# v4m.net
KiCad netlist of a schematic drawn in EAGLE
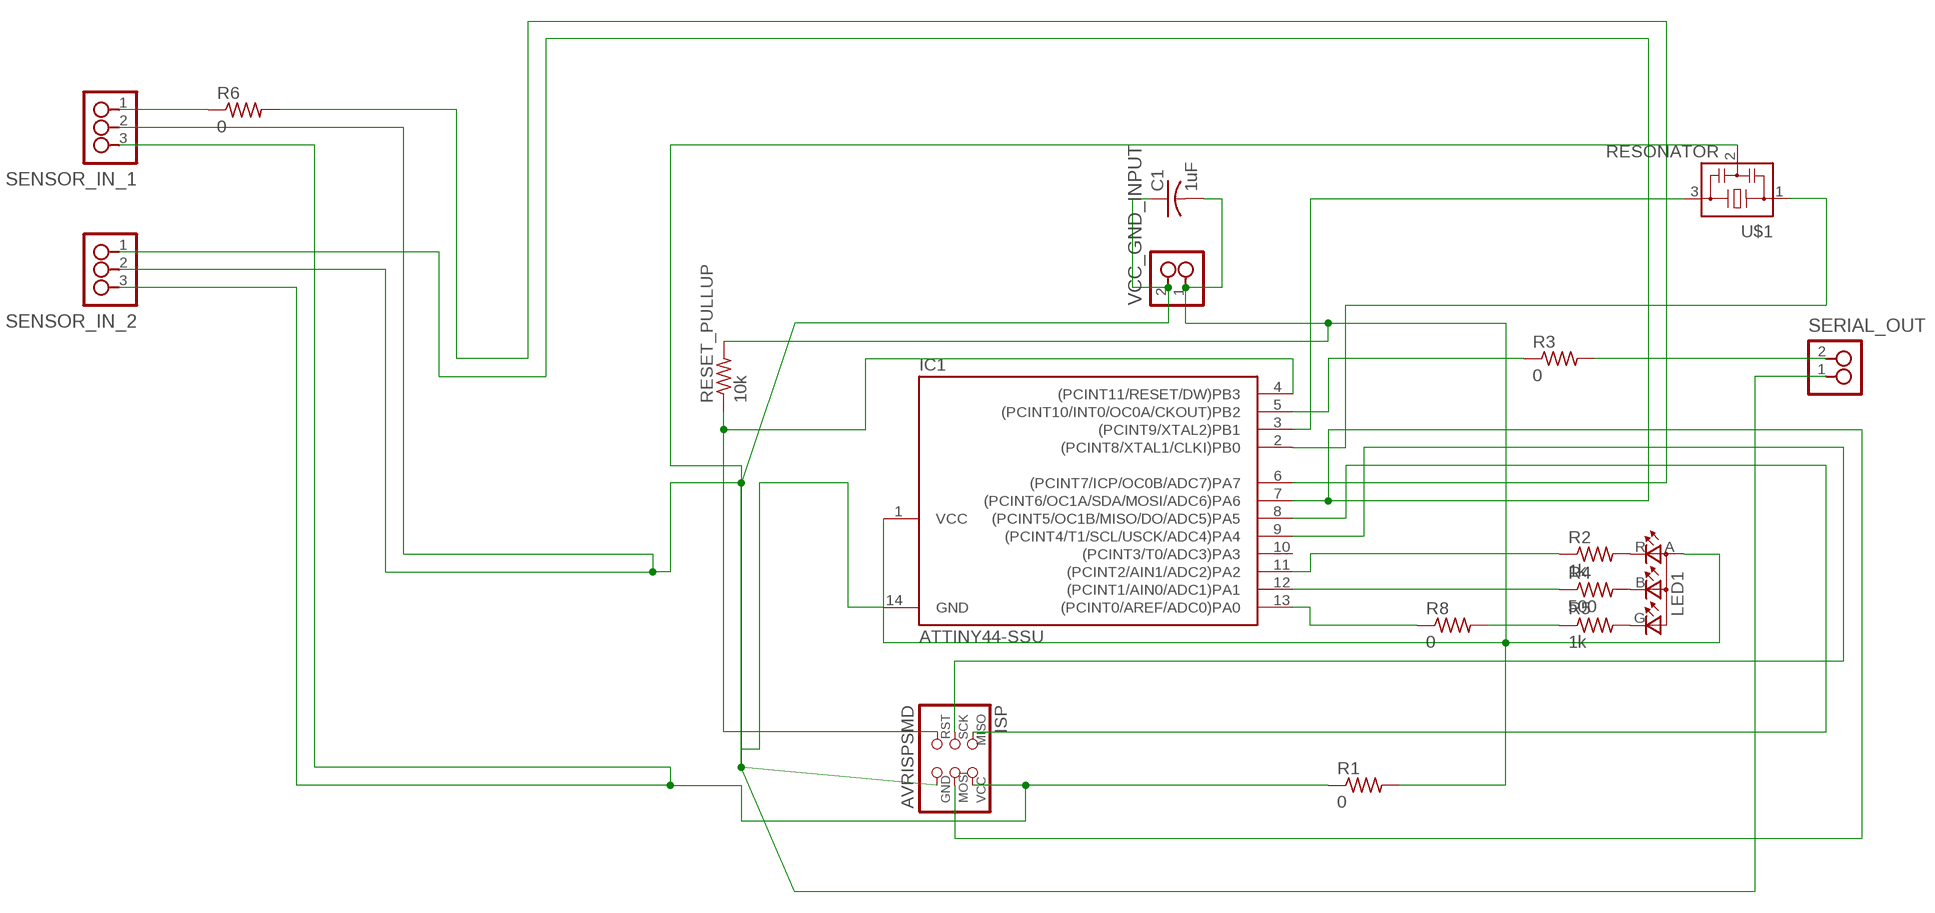
[diagram p0: schematic, sheet 1]

(export (version "E")
  (design (tool "Eeschema 10.0.6"))
  (components
    (comp (ref "C1")
      (value "1uF")
      (footprint "eagle-import:C1206")
      (libsource (lib "eagle-import") (part "C-USC1206"))
    )
    (comp (ref "IC1")
      (value "ATTINY44-SSU")
      (footprint "eagle-import:SOIC14")
      (libsource (lib "eagle-import") (part "ATTINY44-SSU"))
    )
    (comp (ref "ISP")
      (value "AVRISPSMD")
      (footprint "eagle-import:2X03SMD")
      (libsource (lib "eagle-import") (part "AVRISPSMD"))
    )
    (comp (ref "LED1")
      (value "LEDRGBOLD")
      (footprint "eagle-import:P-LCC-4-3")
      (libsource (lib "eagle-import") (part "LEDRGBOLD"))
    )
    (comp (ref "R1")
      (value "0")
      (footprint "eagle-import:R1206")
      (libsource (lib "eagle-import") (part "RES-US1206"))
    )
    (comp (ref "R2")
      (value "1k")
      (footprint "eagle-import:R1206")
      (libsource (lib "eagle-import") (part "RES-US1206"))
    )
    (comp (ref "R3")
      (value "0")
      (footprint "eagle-import:R1206")
      (libsource (lib "eagle-import") (part "RES-US1206"))
    )
    (comp (ref "R4")
      (value "500")
      (footprint "eagle-import:R1206")
      (libsource (lib "eagle-import") (part "RES-US1206"))
    )
    (comp (ref "R5")
      (value "1k")
      (footprint "eagle-import:R1206")
      (libsource (lib "eagle-import") (part "RES-US1206"))
    )
    (comp (ref "R6")
      (value "0")
      (footprint "eagle-import:R1206")
      (libsource (lib "eagle-import") (part "RES-US1206"))
    )
    (comp (ref "R8")
      (value "0")
      (footprint "eagle-import:R1206")
      (libsource (lib "eagle-import") (part "RES-US1206"))
    )
    (comp (ref "RESET_PULLUP")
      (value "10k")
      (footprint "eagle-import:R1206")
      (libsource (lib "eagle-import") (part "R-US_R1206"))
    )
    (comp (ref "SENSOR_IN_1")
      (value "3_PIN_HEADERHEADER")
      (footprint "eagle-import:SMT_PINS_3")
      (libsource (lib "eagle-import") (part "3_PIN_HEADERHEADER"))
    )
    (comp (ref "SENSOR_IN_2")
      (value "3_PIN_HEADERHEADER")
      (footprint "eagle-import:SMT_PINS_3")
      (libsource (lib "eagle-import") (part "3_PIN_HEADERHEADER"))
    )
    (comp (ref "SERIAL_OUT")
      (value "2_PIN_HEADERHEADER")
      (footprint "eagle-import:SMT_PINS_2")
      (libsource (lib "eagle-import") (part "2_PIN_HEADERHEADER"))
    )
    (comp (ref "U$1")
      (value "RESONATOR")
      (footprint "eagle-import:EFOBM")
      (libsource (lib "eagle-import") (part "RESONATOR"))
    )
    (comp (ref "VCC_GND_INPUT")
      (value "2_PIN_HEADERHEADER")
      (footprint "eagle-import:SMT_PINS_2")
      (libsource (lib "eagle-import") (part "2_PIN_HEADERHEADER"))
    )
  )
  (nets
    (net (code "1") (name "Net-(IC1-(PCINT0{slash}AREF{slash}ADC0)PA0)") (class "Default")
      (node (ref "IC1") (pin "13") (pinfunction "(PCINT0/AREF/ADC0)PA0_13") (pintype "bidirectional"))
      (node (ref "R8") (pin "1") (pinfunction "1_1") (pintype "passive"))
    )
    (net (code "2") (name "Net-(IC1-(PCINT1{slash}AIN0{slash}ADC1)PA1)") (class "Default")
      (node (ref "IC1") (pin "12") (pinfunction "(PCINT1/AIN0/ADC1)PA1_12") (pintype "bidirectional"))
      (node (ref "R4") (pin "1") (pinfunction "1_1") (pintype "passive"))
    )
    (net (code "3") (name "Net-(IC1-(PCINT2{slash}AIN1{slash}ADC2)PA2)") (class "Default")
      (node (ref "IC1") (pin "11") (pinfunction "(PCINT2/AIN1/ADC2)PA2_11") (pintype "bidirectional"))
      (node (ref "R2") (pin "1") (pinfunction "1_1") (pintype "passive"))
    )
    (net (code "4") (name "Net-(IC1-(PCINT4{slash}T1{slash}SCL{slash}USCK{slash}ADC4)PA4)") (class "Default")
      (node (ref "IC1") (pin "9") (pinfunction "(PCINT4/T1/SCL/USCK/ADC4)PA4_9") (pintype "bidirectional"))
      (node (ref "ISP") (pin "3") (pinfunction "SCK_3") (pintype "passive"))
    )
    (net (code "5") (name "Net-(IC1-(PCINT5{slash}OC1B{slash}MISO{slash}DO{slash}ADC5)PA5)") (class "Default")
      (node (ref "IC1") (pin "8") (pinfunction "(PCINT5/OC1B/MISO/DO/ADC5)PA5_8") (pintype "bidirectional"))
      (node (ref "ISP") (pin "1") (pinfunction "MISO_1") (pintype "passive"))
    )
    (net (code "6") (name "Net-(IC1-(PCINT6{slash}OC1A{slash}SDA{slash}MOSI{slash}ADC6)PA6)") (class "Default")
      (node (ref "IC1") (pin "7") (pinfunction "(PCINT6/OC1A/SDA/MOSI/ADC6)PA6_7") (pintype "bidirectional"))
      (node (ref "ISP") (pin "4") (pinfunction "MOSI_4") (pintype "passive"))
      (node (ref "SENSOR_IN_2") (pin "1") (pinfunction "P$1_1") (pintype "bidirectional"))
    )
    (net (code "7") (name "Net-(IC1-(PCINT7{slash}ICP{slash}OC0B{slash}ADC7)PA7)") (class "Default")
      (node (ref "IC1") (pin "6") (pinfunction "(PCINT7/ICP/OC0B/ADC7)PA7_6") (pintype "bidirectional"))
      (node (ref "R6") (pin "2") (pinfunction "2_2") (pintype "passive"))
    )
    (net (code "8") (name "Net-(IC1-(PCINT8{slash}XTAL1{slash}CLKI)PB0)") (class "Default")
      (node (ref "IC1") (pin "2") (pinfunction "(PCINT8/XTAL1/CLKI)PB0_2") (pintype "bidirectional"))
      (node (ref "U$1") (pin "1") (pinfunction "1_1") (pintype "passive"))
    )
    (net (code "9") (name "Net-(IC1-(PCINT9{slash}XTAL2)PB1)") (class "Default")
      (node (ref "IC1") (pin "3") (pinfunction "(PCINT9/XTAL2)PB1_3") (pintype "bidirectional"))
      (node (ref "U$1") (pin "3") (pinfunction "3_3") (pintype "passive"))
    )
    (net (code "10") (name "Net-(IC1-(PCINT10{slash}INT0{slash}OC0A{slash}CKOUT)PB2)") (class "Default")
      (node (ref "IC1") (pin "5") (pinfunction "(PCINT10/INT0/OC0A/CKOUT)PB2_5") (pintype "bidirectional"))
      (node (ref "R3") (pin "1") (pinfunction "1_1") (pintype "passive"))
    )
    (net (code "11") (name "Net-(IC1-(PCINT11{slash}RESET{slash}DW)PB3)") (class "Default")
      (node (ref "IC1") (pin "4") (pinfunction "(PCINT11/RESET/DW)PB3_4") (pintype "bidirectional"))
      (node (ref "ISP") (pin "5") (pinfunction "RST_5") (pintype "passive"))
      (node (ref "RESET_PULLUP") (pin "1") (pinfunction "1_1") (pintype "passive"))
    )
    (net (code "12") (name "Net-(IC1-GND)") (class "Default")
      (node (ref "C1") (pin "1") (pinfunction "1_1") (pintype "passive"))
      (node (ref "IC1") (pin "14") (pinfunction "GND_14") (pintype "power_in"))
      (node (ref "ISP") (pin "6") (pinfunction "GND_6") (pintype "passive"))
      (node (ref "SENSOR_IN_1") (pin "2") (pinfunction "P$2_2") (pintype "bidirectional"))
      (node (ref "SENSOR_IN_2") (pin "2") (pinfunction "P$2_2") (pintype "bidirectional"))
      (node (ref "SERIAL_OUT") (pin "1") (pinfunction "1_1") (pintype "bidirectional"))
      (node (ref "U$1") (pin "2") (pinfunction "2_2") (pintype "passive"))
      (node (ref "VCC_GND_INPUT") (pin "2") (pinfunction "2_2") (pintype "bidirectional"))
    )
    (net (code "13") (name "Net-(IC1-VCC)") (class "Default")
      (node (ref "C1") (pin "2") (pinfunction "2_2") (pintype "passive"))
      (node (ref "IC1") (pin "1") (pinfunction "VCC_1") (pintype "power_in"))
      (node (ref "LED1") (pin "A") (pinfunction "A2_A") (pintype "passive"))
      (node (ref "R1") (pin "2") (pinfunction "2_2") (pintype "passive"))
      (node (ref "RESET_PULLUP") (pin "2") (pinfunction "2_2") (pintype "passive"))
      (node (ref "VCC_GND_INPUT") (pin "1") (pinfunction "1_1") (pintype "bidirectional"))
    )
    (net (code "14") (name "Net-(ISP-VCC)") (class "Default")
      (node (ref "ISP") (pin "2") (pinfunction "VCC_2") (pintype "passive"))
      (node (ref "R1") (pin "1") (pinfunction "1_1") (pintype "passive"))
      (node (ref "SENSOR_IN_1") (pin "3") (pinfunction "P$3_3") (pintype "bidirectional"))
      (node (ref "SENSOR_IN_2") (pin "3") (pinfunction "P$3_3") (pintype "bidirectional"))
    )
    (net (code "15") (name "Net-(LED1-CBLUE)") (class "Default")
      (node (ref "LED1") (pin "B") (pinfunction "CBLUE_B") (pintype "passive"))
      (node (ref "R4") (pin "2") (pinfunction "2_2") (pintype "passive"))
    )
    (net (code "16") (name "Net-(LED1-CGREEN)") (class "Default")
      (node (ref "LED1") (pin "G") (pinfunction "CGREEN_G") (pintype "passive"))
      (node (ref "R5") (pin "2") (pinfunction "2_2") (pintype "passive"))
    )
    (net (code "17") (name "Net-(LED1-CRED)") (class "Default")
      (node (ref "LED1") (pin "R") (pinfunction "CRED_R") (pintype "passive"))
      (node (ref "R2") (pin "2") (pinfunction "2_2") (pintype "passive"))
    )
    (net (code "18") (name "Net-(R3-Pad2)") (class "Default")
      (node (ref "R3") (pin "2") (pinfunction "2_2") (pintype "passive"))
      (node (ref "SERIAL_OUT") (pin "2") (pinfunction "2_2") (pintype "bidirectional"))
    )
    (net (code "19") (name "Net-(R5-Pad1)") (class "Default")
      (node (ref "R5") (pin "1") (pinfunction "1_1") (pintype "passive"))
      (node (ref "R8") (pin "2") (pinfunction "2_2") (pintype "passive"))
    )
    (net (code "20") (name "Net-(SENSOR_IN_1-P$1)") (class "Default")
      (node (ref "R6") (pin "1") (pinfunction "1_1") (pintype "passive"))
      (node (ref "SENSOR_IN_1") (pin "1") (pinfunction "P$1_1") (pintype "bidirectional"))
    )
    (net (code "21") (name "unconnected-(IC1-(PCINT3{slash}T0{slash}ADC3)PA3-Pad10)") (class "Default")
      (node (ref "IC1") (pin "10") (pinfunction "(PCINT3/T0/ADC3)PA3_10") (pintype "bidirectional"))
    )
  )
)
